# CPU_-_Ethernet.net
KiCad netlist of a schematic drawn in Altium Designer
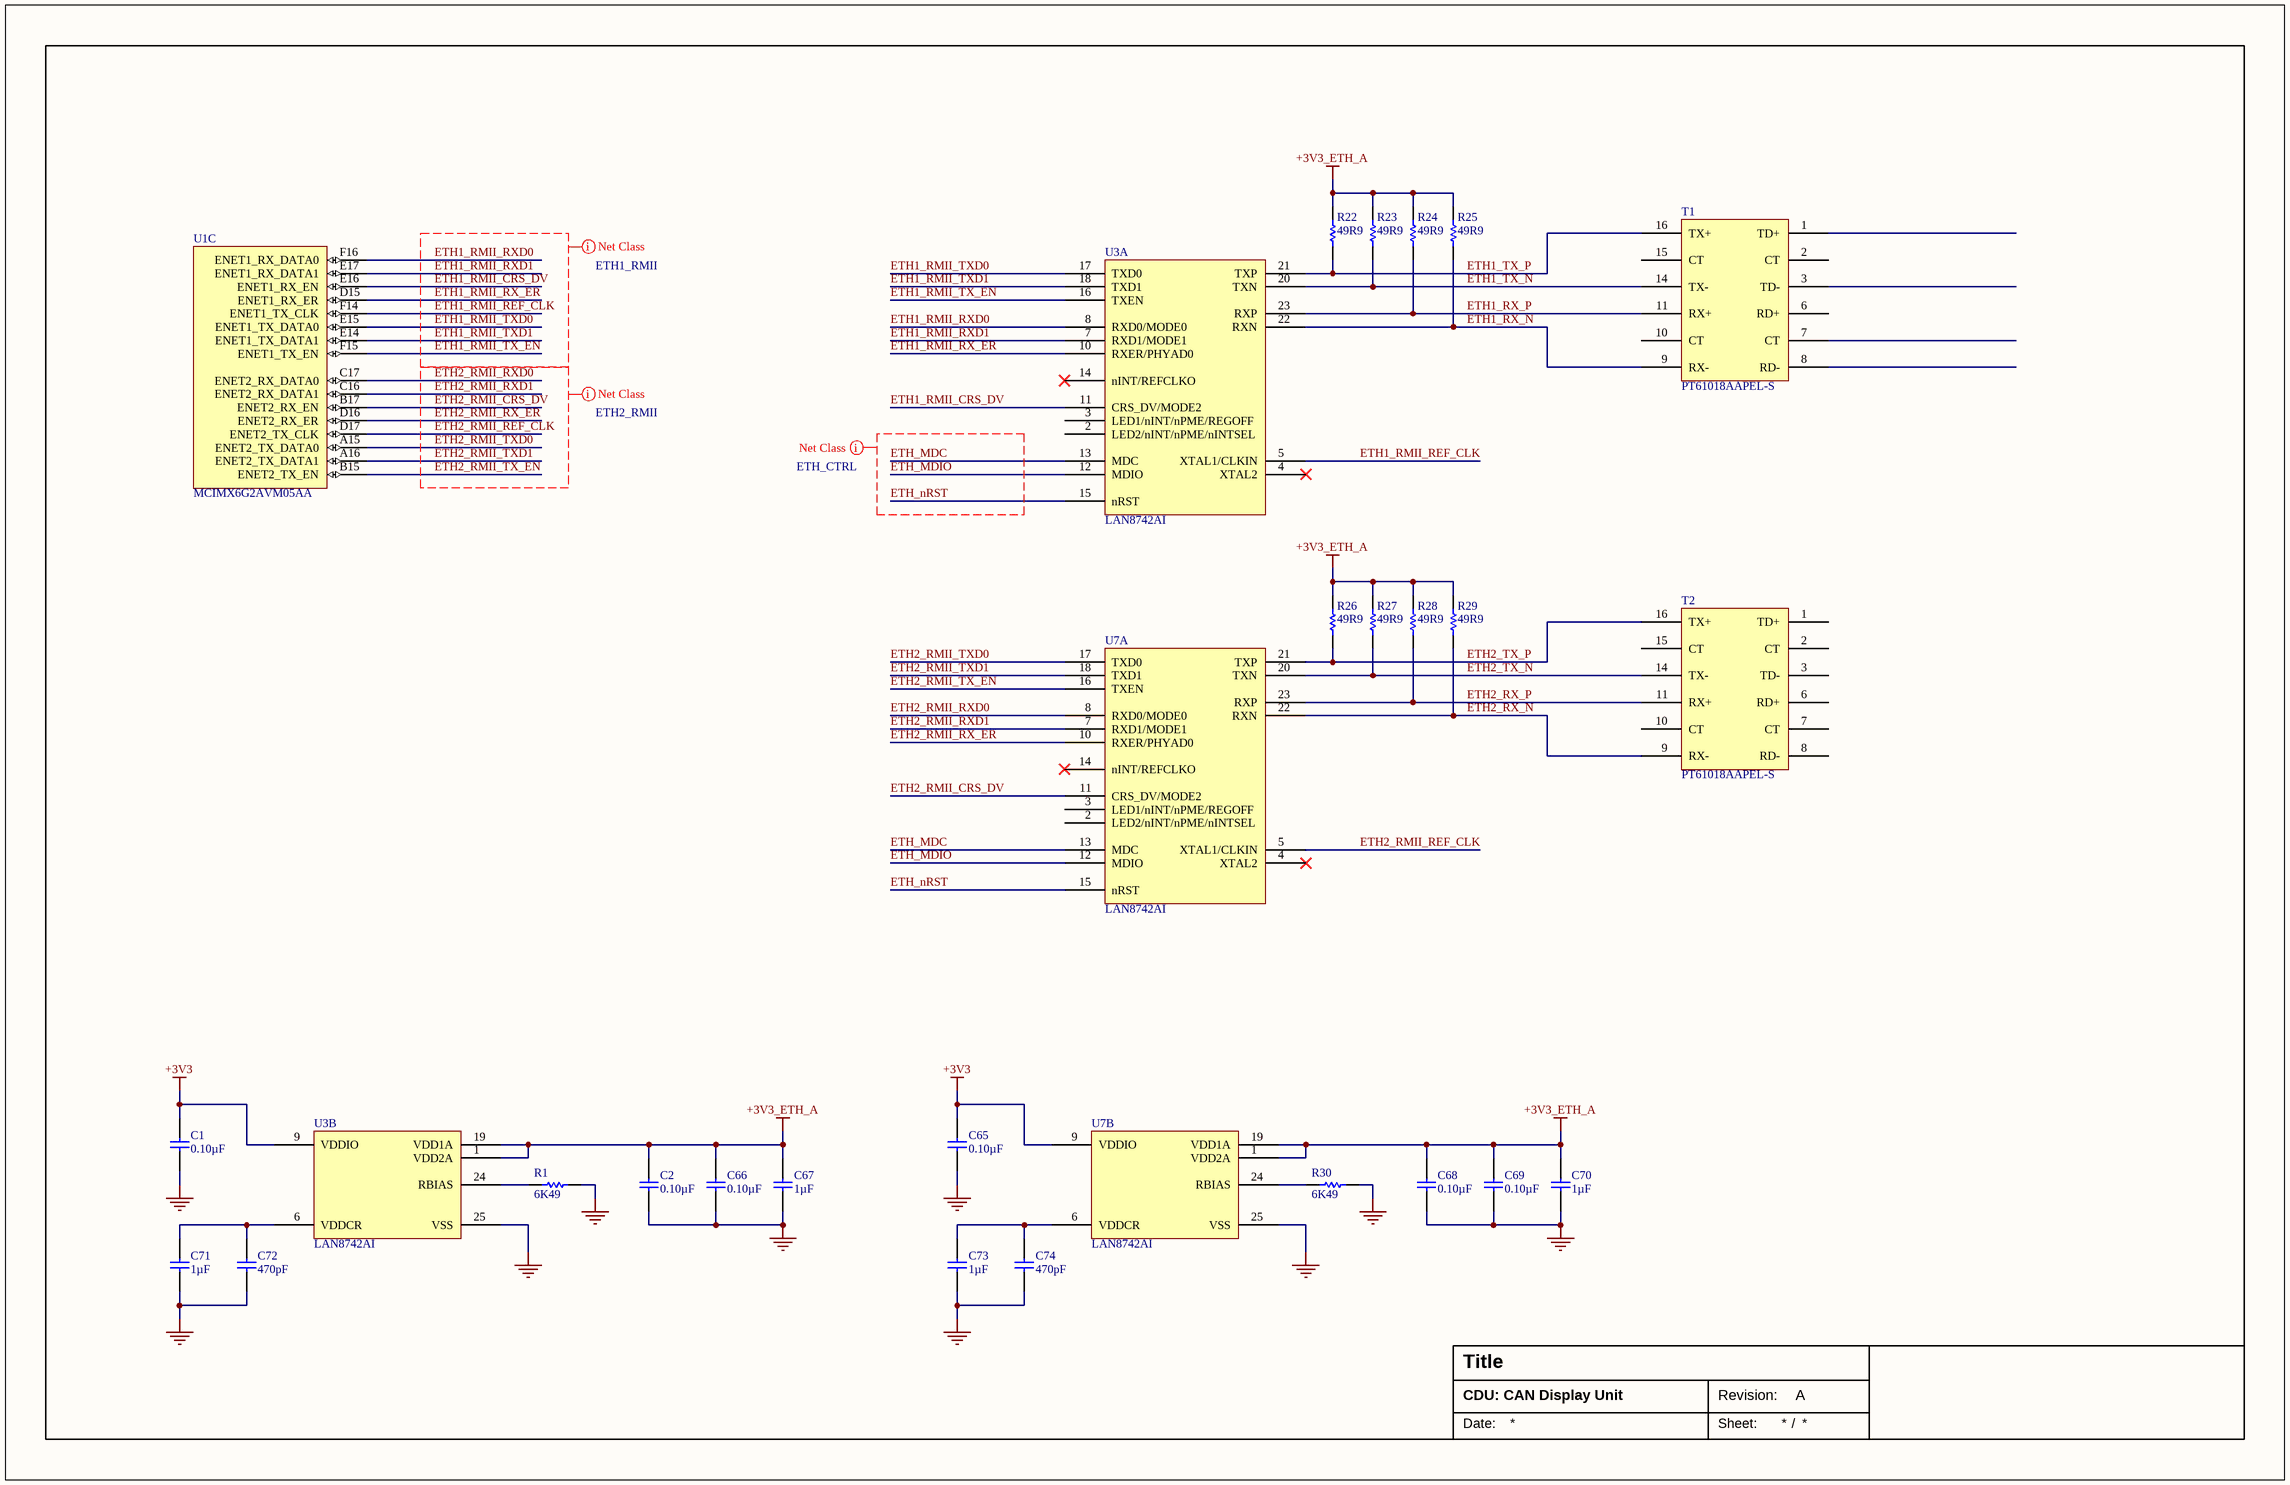
[diagram p0: CPU - Ethernet.SchDoc]

(export (version "E")
  (design (tool "Eeschema 10.0.6"))
  (components
    (comp (ref "C1")
      (value "0.10µF")
      (footprint "CAP-0402-M")
      (fields
        (field (name "PART NUMBER") "CC0402KRX7R8BB104")
        (field (name "TOLERANCE") "±10%")
        (field (name "VOLTAGE") "25V")
      )
      (libsource (lib "Capacitors") (part "Capacitor"))
    )
    (comp (ref "C2")
      (value "0.10µF")
      (footprint "CAP-0402-M")
      (fields
        (field (name "PART NUMBER") "CC0402KRX7R8BB104")
        (field (name "TOLERANCE") "±10%")
        (field (name "VOLTAGE") "25V")
      )
      (libsource (lib "Capacitors") (part "Capacitor"))
    )
    (comp (ref "C65")
      (value "0.10µF")
      (footprint "CAP-0402-M")
      (fields
        (field (name "PART NUMBER") "CC0402KRX7R8BB104")
        (field (name "TOLERANCE") "±10%")
        (field (name "VOLTAGE") "25V")
      )
      (libsource (lib "Capacitors") (part "Capacitor"))
    )
    (comp (ref "C66")
      (value "0.10µF")
      (footprint "CAP-0402-M")
      (fields
        (field (name "PART NUMBER") "CC0402KRX7R8BB104")
        (field (name "TOLERANCE") "±10%")
        (field (name "VOLTAGE") "25V")
      )
      (libsource (lib "Capacitors") (part "Capacitor"))
    )
    (comp (ref "C67")
      (value "1µF")
      (footprint "CAP-0402-M")
      (fields
        (field (name "PART NUMBER") "CC0402KRX7R5BB105")
        (field (name "TOLERANCE") "±10%")
        (field (name "VOLTAGE") "6.3V")
      )
      (libsource (lib "Capacitors") (part "Capacitor"))
    )
    (comp (ref "C68")
      (value "0.10µF")
      (footprint "CAP-0402-M")
      (fields
        (field (name "PART NUMBER") "CC0402KRX7R8BB104")
        (field (name "TOLERANCE") "±10%")
        (field (name "VOLTAGE") "25V")
      )
      (libsource (lib "Capacitors") (part "Capacitor"))
    )
    (comp (ref "C69")
      (value "0.10µF")
      (footprint "CAP-0402-M")
      (fields
        (field (name "PART NUMBER") "CC0402KRX7R8BB104")
        (field (name "TOLERANCE") "±10%")
        (field (name "VOLTAGE") "25V")
      )
      (libsource (lib "Capacitors") (part "Capacitor"))
    )
    (comp (ref "C70")
      (value "1µF")
      (footprint "CAP-0402-M")
      (fields
        (field (name "PART NUMBER") "CC0402KRX7R5BB105")
        (field (name "TOLERANCE") "±10%")
        (field (name "VOLTAGE") "6.3V")
      )
      (libsource (lib "Capacitors") (part "Capacitor"))
    )
    (comp (ref "C71")
      (value "1µF")
      (footprint "CAP-0402-M")
      (fields
        (field (name "PART NUMBER") "CC0402KRX7R5BB105")
        (field (name "TOLERANCE") "±10%")
        (field (name "VOLTAGE") "6.3V")
      )
      (libsource (lib "Capacitors") (part "Capacitor"))
    )
    (comp (ref "C72")
      (value "470pF")
      (footprint "CAP-0402-M")
      (fields
        (field (name "PART NUMBER") "CC0402JRNPO9BN471")
        (field (name "TOLERANCE") "±5%")
        (field (name "VOLTAGE") "50V")
      )
      (libsource (lib "Capacitors") (part "Capacitor"))
    )
    (comp (ref "C73")
      (value "1µF")
      (footprint "CAP-0402-M")
      (fields
        (field (name "PART NUMBER") "CC0402KRX7R5BB105")
        (field (name "TOLERANCE") "±10%")
        (field (name "VOLTAGE") "6.3V")
      )
      (libsource (lib "Capacitors") (part "Capacitor"))
    )
    (comp (ref "C74")
      (value "470pF")
      (footprint "CAP-0402-M")
      (fields
        (field (name "PART NUMBER") "CC0402JRNPO9BN471")
        (field (name "TOLERANCE") "±5%")
        (field (name "VOLTAGE") "50V")
      )
      (libsource (lib "Capacitors") (part "Capacitor"))
    )
    (comp (ref "R1")
      (value "6K49")
      (footprint "RES-0603-M")
      (fields
        (field (name "PART NUMBER") "RC0603FR-076K49L")
        (field (name "TOLERANCE") "1%")
        (field (name "POWER") "1/10 W")
      )
      (libsource (lib "Resistors") (part "Resistor"))
    )
    (comp (ref "R22")
      (value "49R9")
      (footprint "RES-0402-M")
      (fields
        (field (name "PART NUMBER") "RC0402FR-0749R9L")
        (field (name "TOLERANCE") "1%")
        (field (name "POWER") "1/16W")
      )
      (libsource (lib "Resistors") (part "Resistor"))
    )
    (comp (ref "R23")
      (value "49R9")
      (footprint "RES-0402-M")
      (fields
        (field (name "PART NUMBER") "RC0402FR-0749R9L")
        (field (name "TOLERANCE") "1%")
        (field (name "POWER") "1/16W")
      )
      (libsource (lib "Resistors") (part "Resistor"))
    )
    (comp (ref "R24")
      (value "49R9")
      (footprint "RES-0402-M")
      (fields
        (field (name "PART NUMBER") "RC0402FR-0749R9L")
        (field (name "TOLERANCE") "1%")
        (field (name "POWER") "1/16W")
      )
      (libsource (lib "Resistors") (part "Resistor"))
    )
    (comp (ref "R25")
      (value "49R9")
      (footprint "RES-0402-M")
      (fields
        (field (name "PART NUMBER") "RC0402FR-0749R9L")
        (field (name "TOLERANCE") "1%")
        (field (name "POWER") "1/16W")
      )
      (libsource (lib "Resistors") (part "Resistor"))
    )
    (comp (ref "R26")
      (value "49R9")
      (footprint "RES-0402-M")
      (fields
        (field (name "PART NUMBER") "RC0402FR-0749R9L")
        (field (name "TOLERANCE") "1%")
        (field (name "POWER") "1/16W")
      )
      (libsource (lib "Resistors") (part "Resistor"))
    )
    (comp (ref "R27")
      (value "49R9")
      (footprint "RES-0402-M")
      (fields
        (field (name "PART NUMBER") "RC0402FR-0749R9L")
        (field (name "TOLERANCE") "1%")
        (field (name "POWER") "1/16W")
      )
      (libsource (lib "Resistors") (part "Resistor"))
    )
    (comp (ref "R28")
      (value "49R9")
      (footprint "RES-0402-M")
      (fields
        (field (name "PART NUMBER") "RC0402FR-0749R9L")
        (field (name "TOLERANCE") "1%")
        (field (name "POWER") "1/16W")
      )
      (libsource (lib "Resistors") (part "Resistor"))
    )
    (comp (ref "R29")
      (value "49R9")
      (footprint "RES-0402-M")
      (fields
        (field (name "PART NUMBER") "RC0402FR-0749R9L")
        (field (name "TOLERANCE") "1%")
        (field (name "POWER") "1/16W")
      )
      (libsource (lib "Resistors") (part "Resistor"))
    )
    (comp (ref "R30")
      (value "6K49")
      (footprint "RES-0603-M")
      (fields
        (field (name "PART NUMBER") "RC0603FR-076K49L")
        (field (name "TOLERANCE") "1%")
        (field (name "POWER") "1/10 W")
      )
      (libsource (lib "Resistors") (part "Resistor"))
    )
    (comp (ref "T1")
      (value "PT61018AAPEL-S")
      (footprint "SOIC127P930X590-16N")
      (libsource (lib "Hub-UV17") (part "PT61018AAPEL-S"))
    )
    (comp (ref "T2")
      (value "PT61018AAPEL-S")
      (footprint "SOIC127P930X590-16N")
      (libsource (lib "Hub-UV17") (part "PT61018AAPEL-S"))
    )
    (comp (ref "U1")
      (value "MCIMX6G2AVM05AA")
      (footprint "BGA289C80P17X17_1400X1400X132")
      (libsource (lib "Hub-UV17") (part "MCIMX6G2AVM05AA"))
    )
    (comp (ref "U3")
      (value "LAN8742AI")
      (footprint "QFN50P400X400X100_HS-25N")
      (libsource (lib "Hub-UV17") (part "LAN8742AI"))
    )
    (comp (ref "U7")
      (value "LAN8742AI")
      (footprint "QFN50P400X400X100_HS-25N")
      (libsource (lib "Hub-UV17") (part "LAN8742AI"))
    )
  )
  (nets
    (net (code "1") (name "+3V3") (class "Default")
      (node (ref "C1") (pin "2") (pinfunction "2_2") (pintype "passive"))
      (node (ref "C65") (pin "2") (pinfunction "2_2") (pintype "passive"))
      (node (ref "U3") (pin "9") (pinfunction "VDDIO_9") (pintype "passive"))
      (node (ref "U7") (pin "9") (pinfunction "VDDIO_9") (pintype "passive"))
    )
    (net (code "2") (name "+3V3_ETH_A") (class "Default")
      (node (ref "C2") (pin "2") (pinfunction "2_2") (pintype "passive"))
      (node (ref "C66") (pin "2") (pinfunction "2_2") (pintype "passive"))
      (node (ref "C67") (pin "2") (pinfunction "2_2") (pintype "passive"))
      (node (ref "C68") (pin "2") (pinfunction "2_2") (pintype "passive"))
      (node (ref "C69") (pin "2") (pinfunction "2_2") (pintype "passive"))
      (node (ref "C70") (pin "2") (pinfunction "2_2") (pintype "passive"))
      (node (ref "R22") (pin "2") (pinfunction "2_2") (pintype "passive"))
      (node (ref "R23") (pin "2") (pinfunction "2_2") (pintype "passive"))
      (node (ref "R24") (pin "2") (pinfunction "2_2") (pintype "passive"))
      (node (ref "R25") (pin "2") (pinfunction "2_2") (pintype "passive"))
      (node (ref "R26") (pin "2") (pinfunction "2_2") (pintype "passive"))
      (node (ref "R27") (pin "2") (pinfunction "2_2") (pintype "passive"))
      (node (ref "R28") (pin "2") (pinfunction "2_2") (pintype "passive"))
      (node (ref "R29") (pin "2") (pinfunction "2_2") (pintype "passive"))
      (node (ref "U3") (pin "1") (pinfunction "VDD2A_1") (pintype "passive"))
      (node (ref "U3") (pin "19") (pinfunction "VDD1A_19") (pintype "passive"))
      (node (ref "U7") (pin "1") (pinfunction "VDD2A_1") (pintype "passive"))
      (node (ref "U7") (pin "19") (pinfunction "VDD1A_19") (pintype "passive"))
    )
    (net (code "3") (name "/ETH1_RMII_CRS_DV") (class "Default")
      (node (ref "U1") (pin "E16") (pinfunction "ENET1_RX_EN_E16") (pintype "bidirectional"))
      (node (ref "U3") (pin "11") (pinfunction "CRS_DV/MODE2_11") (pintype "passive"))
    )
    (net (code "4") (name "/ETH1_RMII_REF_CLK") (class "Default")
      (node (ref "U1") (pin "F14") (pinfunction "ENET1_TX_CLK_F14") (pintype "bidirectional"))
      (node (ref "U3") (pin "5") (pinfunction "XTAL1/CLKIN_5") (pintype "passive"))
    )
    (net (code "5") (name "/ETH1_RMII_RXD0") (class "Default")
      (node (ref "U1") (pin "F16") (pinfunction "ENET1_RX_DATA0_F16") (pintype "bidirectional"))
      (node (ref "U3") (pin "8") (pinfunction "RXD0/MODE0_8") (pintype "passive"))
    )
    (net (code "6") (name "/ETH1_RMII_RXD1") (class "Default")
      (node (ref "U1") (pin "E17") (pinfunction "ENET1_RX_DATA1_E17") (pintype "bidirectional"))
      (node (ref "U3") (pin "7") (pinfunction "RXD1/MODE1_7") (pintype "passive"))
    )
    (net (code "7") (name "/ETH1_RMII_RX_ER") (class "Default")
      (node (ref "U1") (pin "D15") (pinfunction "ENET1_RX_ER_D15") (pintype "bidirectional"))
      (node (ref "U3") (pin "10") (pinfunction "RXER/PHYAD0_10") (pintype "passive"))
    )
    (net (code "8") (name "/ETH1_RMII_TXD0") (class "Default")
      (node (ref "U1") (pin "E15") (pinfunction "ENET1_TX_DATA0_E15") (pintype "bidirectional"))
      (node (ref "U3") (pin "17") (pinfunction "TXD0_17") (pintype "passive"))
    )
    (net (code "9") (name "/ETH1_RMII_TXD1") (class "Default")
      (node (ref "U1") (pin "E14") (pinfunction "ENET1_TX_DATA1_E14") (pintype "bidirectional"))
      (node (ref "U3") (pin "18") (pinfunction "TXD1_18") (pintype "passive"))
    )
    (net (code "10") (name "/ETH1_RMII_TX_EN") (class "Default")
      (node (ref "U1") (pin "F15") (pinfunction "ENET1_TX_EN_F15") (pintype "bidirectional"))
      (node (ref "U3") (pin "16") (pinfunction "TXEN_16") (pintype "passive"))
    )
    (net (code "11") (name "/ETH1_RX_N") (class "Default")
      (node (ref "R25") (pin "1") (pinfunction "1_1") (pintype "passive"))
      (node (ref "T1") (pin "9") (pinfunction "RX-_9") (pintype "passive"))
      (node (ref "U3") (pin "22") (pinfunction "RXN_22") (pintype "passive"))
    )
    (net (code "12") (name "/ETH1_RX_P") (class "Default")
      (node (ref "R24") (pin "1") (pinfunction "1_1") (pintype "passive"))
      (node (ref "T1") (pin "11") (pinfunction "RX+_11") (pintype "passive"))
      (node (ref "U3") (pin "23") (pinfunction "RXP_23") (pintype "passive"))
    )
    (net (code "13") (name "/ETH1_TX_N") (class "Default")
      (node (ref "R23") (pin "1") (pinfunction "1_1") (pintype "passive"))
      (node (ref "T1") (pin "14") (pinfunction "TX-_14") (pintype "passive"))
      (node (ref "U3") (pin "20") (pinfunction "TXN_20") (pintype "passive"))
    )
    (net (code "14") (name "/ETH1_TX_P") (class "Default")
      (node (ref "R22") (pin "1") (pinfunction "1_1") (pintype "passive"))
      (node (ref "T1") (pin "16") (pinfunction "TX+_16") (pintype "passive"))
      (node (ref "U3") (pin "21") (pinfunction "TXP_21") (pintype "passive"))
    )
    (net (code "15") (name "/ETH2_RMII_CRS_DV") (class "Default")
      (node (ref "U1") (pin "B17") (pinfunction "ENET2_RX_EN_B17") (pintype "bidirectional"))
      (node (ref "U7") (pin "11") (pinfunction "CRS_DV/MODE2_11") (pintype "passive"))
    )
    (net (code "16") (name "/ETH2_RMII_REF_CLK") (class "Default")
      (node (ref "U1") (pin "D17") (pinfunction "ENET2_TX_CLK_D17") (pintype "bidirectional"))
      (node (ref "U7") (pin "5") (pinfunction "XTAL1/CLKIN_5") (pintype "passive"))
    )
    (net (code "17") (name "/ETH2_RMII_RXD0") (class "Default")
      (node (ref "U1") (pin "C17") (pinfunction "ENET2_RX_DATA0_C17") (pintype "bidirectional"))
      (node (ref "U7") (pin "8") (pinfunction "RXD0/MODE0_8") (pintype "passive"))
    )
    (net (code "18") (name "/ETH2_RMII_RXD1") (class "Default")
      (node (ref "U1") (pin "C16") (pinfunction "ENET2_RX_DATA1_C16") (pintype "bidirectional"))
      (node (ref "U7") (pin "7") (pinfunction "RXD1/MODE1_7") (pintype "passive"))
    )
    (net (code "19") (name "/ETH2_RMII_RX_ER") (class "Default")
      (node (ref "U1") (pin "D16") (pinfunction "ENET2_RX_ER_D16") (pintype "bidirectional"))
      (node (ref "U7") (pin "10") (pinfunction "RXER/PHYAD0_10") (pintype "passive"))
    )
    (net (code "20") (name "/ETH2_RMII_TXD0") (class "Default")
      (node (ref "U1") (pin "A15") (pinfunction "ENET2_TX_DATA0_A15") (pintype "bidirectional"))
      (node (ref "U7") (pin "17") (pinfunction "TXD0_17") (pintype "passive"))
    )
    (net (code "21") (name "/ETH2_RMII_TXD1") (class "Default")
      (node (ref "U1") (pin "A16") (pinfunction "ENET2_TX_DATA1_A16") (pintype "bidirectional"))
      (node (ref "U7") (pin "18") (pinfunction "TXD1_18") (pintype "passive"))
    )
    (net (code "22") (name "/ETH2_RMII_TX_EN") (class "Default")
      (node (ref "U1") (pin "B15") (pinfunction "ENET2_TX_EN_B15") (pintype "bidirectional"))
      (node (ref "U7") (pin "16") (pinfunction "TXEN_16") (pintype "passive"))
    )
    (net (code "23") (name "/ETH2_RX_N") (class "Default")
      (node (ref "R29") (pin "1") (pinfunction "1_1") (pintype "passive"))
      (node (ref "T2") (pin "9") (pinfunction "RX-_9") (pintype "passive"))
      (node (ref "U7") (pin "22") (pinfunction "RXN_22") (pintype "passive"))
    )
    (net (code "24") (name "/ETH2_RX_P") (class "Default")
      (node (ref "R28") (pin "1") (pinfunction "1_1") (pintype "passive"))
      (node (ref "T2") (pin "11") (pinfunction "RX+_11") (pintype "passive"))
      (node (ref "U7") (pin "23") (pinfunction "RXP_23") (pintype "passive"))
    )
    (net (code "25") (name "/ETH2_TX_N") (class "Default")
      (node (ref "R27") (pin "1") (pinfunction "1_1") (pintype "passive"))
      (node (ref "T2") (pin "14") (pinfunction "TX-_14") (pintype "passive"))
      (node (ref "U7") (pin "20") (pinfunction "TXN_20") (pintype "passive"))
    )
    (net (code "26") (name "/ETH2_TX_P") (class "Default")
      (node (ref "R26") (pin "1") (pinfunction "1_1") (pintype "passive"))
      (node (ref "T2") (pin "16") (pinfunction "TX+_16") (pintype "passive"))
      (node (ref "U7") (pin "21") (pinfunction "TXP_21") (pintype "passive"))
    )
    (net (code "27") (name "/ETH_MDC") (class "Default")
      (node (ref "U3") (pin "13") (pinfunction "MDC_13") (pintype "passive"))
      (node (ref "U7") (pin "13") (pinfunction "MDC_13") (pintype "passive"))
    )
    (net (code "28") (name "/ETH_MDIO") (class "Default")
      (node (ref "U3") (pin "12") (pinfunction "MDIO_12") (pintype "passive"))
      (node (ref "U7") (pin "12") (pinfunction "MDIO_12") (pintype "passive"))
    )
    (net (code "29") (name "/ETH_nRST") (class "Default")
      (node (ref "U3") (pin "15") (pinfunction "nRST_15") (pintype "passive"))
      (node (ref "U7") (pin "15") (pinfunction "nRST_15") (pintype "passive"))
    )
    (net (code "30") (name "GND") (class "Default")
      (node (ref "C1") (pin "1") (pinfunction "1_1") (pintype "passive"))
      (node (ref "C2") (pin "1") (pinfunction "1_1") (pintype "passive"))
      (node (ref "C65") (pin "1") (pinfunction "1_1") (pintype "passive"))
      (node (ref "C66") (pin "1") (pinfunction "1_1") (pintype "passive"))
      (node (ref "C67") (pin "1") (pinfunction "1_1") (pintype "passive"))
      (node (ref "C68") (pin "1") (pinfunction "1_1") (pintype "passive"))
      (node (ref "C69") (pin "1") (pinfunction "1_1") (pintype "passive"))
      (node (ref "C70") (pin "1") (pinfunction "1_1") (pintype "passive"))
      (node (ref "C71") (pin "1") (pinfunction "1_1") (pintype "passive"))
      (node (ref "C72") (pin "1") (pinfunction "1_1") (pintype "passive"))
      (node (ref "C73") (pin "1") (pinfunction "1_1") (pintype "passive"))
      (node (ref "C74") (pin "1") (pinfunction "1_1") (pintype "passive"))
      (node (ref "R1") (pin "1") (pinfunction "1_1") (pintype "passive"))
      (node (ref "R30") (pin "1") (pinfunction "1_1") (pintype "passive"))
      (node (ref "U3") (pin "25") (pinfunction "VSS_25") (pintype "passive"))
      (node (ref "U7") (pin "25") (pinfunction "VSS_25") (pintype "passive"))
    )
    (net (code "31") (name "Net-(U3B-RBIAS)") (class "Default")
      (node (ref "R1") (pin "2") (pinfunction "2_2") (pintype "passive"))
      (node (ref "U3") (pin "24") (pinfunction "RBIAS_24") (pintype "passive"))
    )
    (net (code "32") (name "Net-(U3B-VDDCR)") (class "Default")
      (node (ref "C71") (pin "2") (pinfunction "2_2") (pintype "passive"))
      (node (ref "C72") (pin "2") (pinfunction "2_2") (pintype "passive"))
      (node (ref "U3") (pin "6") (pinfunction "VDDCR_6") (pintype "passive"))
    )
    (net (code "33") (name "Net-(U7B-RBIAS)") (class "Default")
      (node (ref "R30") (pin "2") (pinfunction "2_2") (pintype "passive"))
      (node (ref "U7") (pin "24") (pinfunction "RBIAS_24") (pintype "passive"))
    )
    (net (code "34") (name "Net-(U7B-VDDCR)") (class "Default")
      (node (ref "C73") (pin "2") (pinfunction "2_2") (pintype "passive"))
      (node (ref "C74") (pin "2") (pinfunction "2_2") (pintype "passive"))
      (node (ref "U7") (pin "6") (pinfunction "VDDCR_6") (pintype "passive"))
    )
    (net (code "35") (name "unconnected-(T1-CT-Pad2)") (class "Default")
      (node (ref "T1") (pin "2") (pinfunction "CT_2") (pintype "passive"))
    )
    (net (code "36") (name "unconnected-(T1-CT-Pad7)") (class "Default")
      (node (ref "T1") (pin "7") (pinfunction "CT_7") (pintype "passive"))
    )
    (net (code "37") (name "unconnected-(T1-CT-Pad10)") (class "Default")
      (node (ref "T1") (pin "10") (pinfunction "CT_10") (pintype "passive"))
    )
    (net (code "38") (name "unconnected-(T1-CT-Pad15)") (class "Default")
      (node (ref "T1") (pin "15") (pinfunction "CT_15") (pintype "passive"))
    )
    (net (code "39") (name "unconnected-(T1-RD+-Pad6)") (class "Default")
      (node (ref "T1") (pin "6") (pinfunction "RD+_6") (pintype "passive"))
    )
    (net (code "40") (name "unconnected-(T1-RD--Pad8)") (class "Default")
      (node (ref "T1") (pin "8") (pinfunction "RD-_8") (pintype "passive"))
    )
    (net (code "41") (name "unconnected-(T1-TD+-Pad1)") (class "Default")
      (node (ref "T1") (pin "1") (pinfunction "TD+_1") (pintype "passive"))
    )
    (net (code "42") (name "unconnected-(T1-TD--Pad3)") (class "Default")
      (node (ref "T1") (pin "3") (pinfunction "TD-_3") (pintype "passive"))
    )
    (net (code "43") (name "unconnected-(T2-CT-Pad2)") (class "Default")
      (node (ref "T2") (pin "2") (pinfunction "CT_2") (pintype "passive"))
    )
    (net (code "44") (name "unconnected-(T2-CT-Pad7)") (class "Default")
      (node (ref "T2") (pin "7") (pinfunction "CT_7") (pintype "passive"))
    )
    (net (code "45") (name "unconnected-(T2-CT-Pad10)") (class "Default")
      (node (ref "T2") (pin "10") (pinfunction "CT_10") (pintype "passive"))
    )
    (net (code "46") (name "unconnected-(T2-CT-Pad15)") (class "Default")
      (node (ref "T2") (pin "15") (pinfunction "CT_15") (pintype "passive"))
    )
    (net (code "47") (name "unconnected-(T2-RD+-Pad6)") (class "Default")
      (node (ref "T2") (pin "6") (pinfunction "RD+_6") (pintype "passive"))
    )
    (net (code "48") (name "unconnected-(T2-RD--Pad8)") (class "Default")
      (node (ref "T2") (pin "8") (pinfunction "RD-_8") (pintype "passive"))
    )
    (net (code "49") (name "unconnected-(T2-TD+-Pad1)") (class "Default")
      (node (ref "T2") (pin "1") (pinfunction "TD+_1") (pintype "passive"))
    )
    (net (code "50") (name "unconnected-(T2-TD--Pad3)") (class "Default")
      (node (ref "T2") (pin "3") (pinfunction "TD-_3") (pintype "passive"))
    )
    (net (code "51") (name "unconnected-(U3A-LED1{slash}nINT{slash}nPME{slash}REGOFF-Pad3)") (class "Default")
      (node (ref "U3") (pin "3") (pinfunction "LED1/nINT/nPME/REGOFF_3") (pintype "passive"))
    )
    (net (code "52") (name "unconnected-(U3A-LED2{slash}nINT{slash}nPME{slash}nINTSEL-Pad2)") (class "Default")
      (node (ref "U3") (pin "2") (pinfunction "LED2/nINT/nPME/nINTSEL_2") (pintype "passive"))
    )
    (net (code "53") (name "unconnected-(U3A-XTAL2-Pad4)") (class "Default")
      (node (ref "U3") (pin "4") (pinfunction "XTAL2_4") (pintype "passive+no_connect"))
    )
    (net (code "54") (name "unconnected-(U3A-nINT{slash}REFCLKO-Pad14)") (class "Default")
      (node (ref "U3") (pin "14") (pinfunction "nINT/REFCLKO_14") (pintype "passive+no_connect"))
    )
    (net (code "55") (name "unconnected-(U7A-LED1{slash}nINT{slash}nPME{slash}REGOFF-Pad3)") (class "Default")
      (node (ref "U7") (pin "3") (pinfunction "LED1/nINT/nPME/REGOFF_3") (pintype "passive"))
    )
    (net (code "56") (name "unconnected-(U7A-LED2{slash}nINT{slash}nPME{slash}nINTSEL-Pad2)") (class "Default")
      (node (ref "U7") (pin "2") (pinfunction "LED2/nINT/nPME/nINTSEL_2") (pintype "passive"))
    )
    (net (code "57") (name "unconnected-(U7A-XTAL2-Pad4)") (class "Default")
      (node (ref "U7") (pin "4") (pinfunction "XTAL2_4") (pintype "passive+no_connect"))
    )
    (net (code "58") (name "unconnected-(U7A-nINT{slash}REFCLKO-Pad14)") (class "Default")
      (node (ref "U7") (pin "14") (pinfunction "nINT/REFCLKO_14") (pintype "passive+no_connect"))
    )
  )
)
